# proiect_tsc_v49.net
KiCad netlist of a schematic drawn in EAGLE
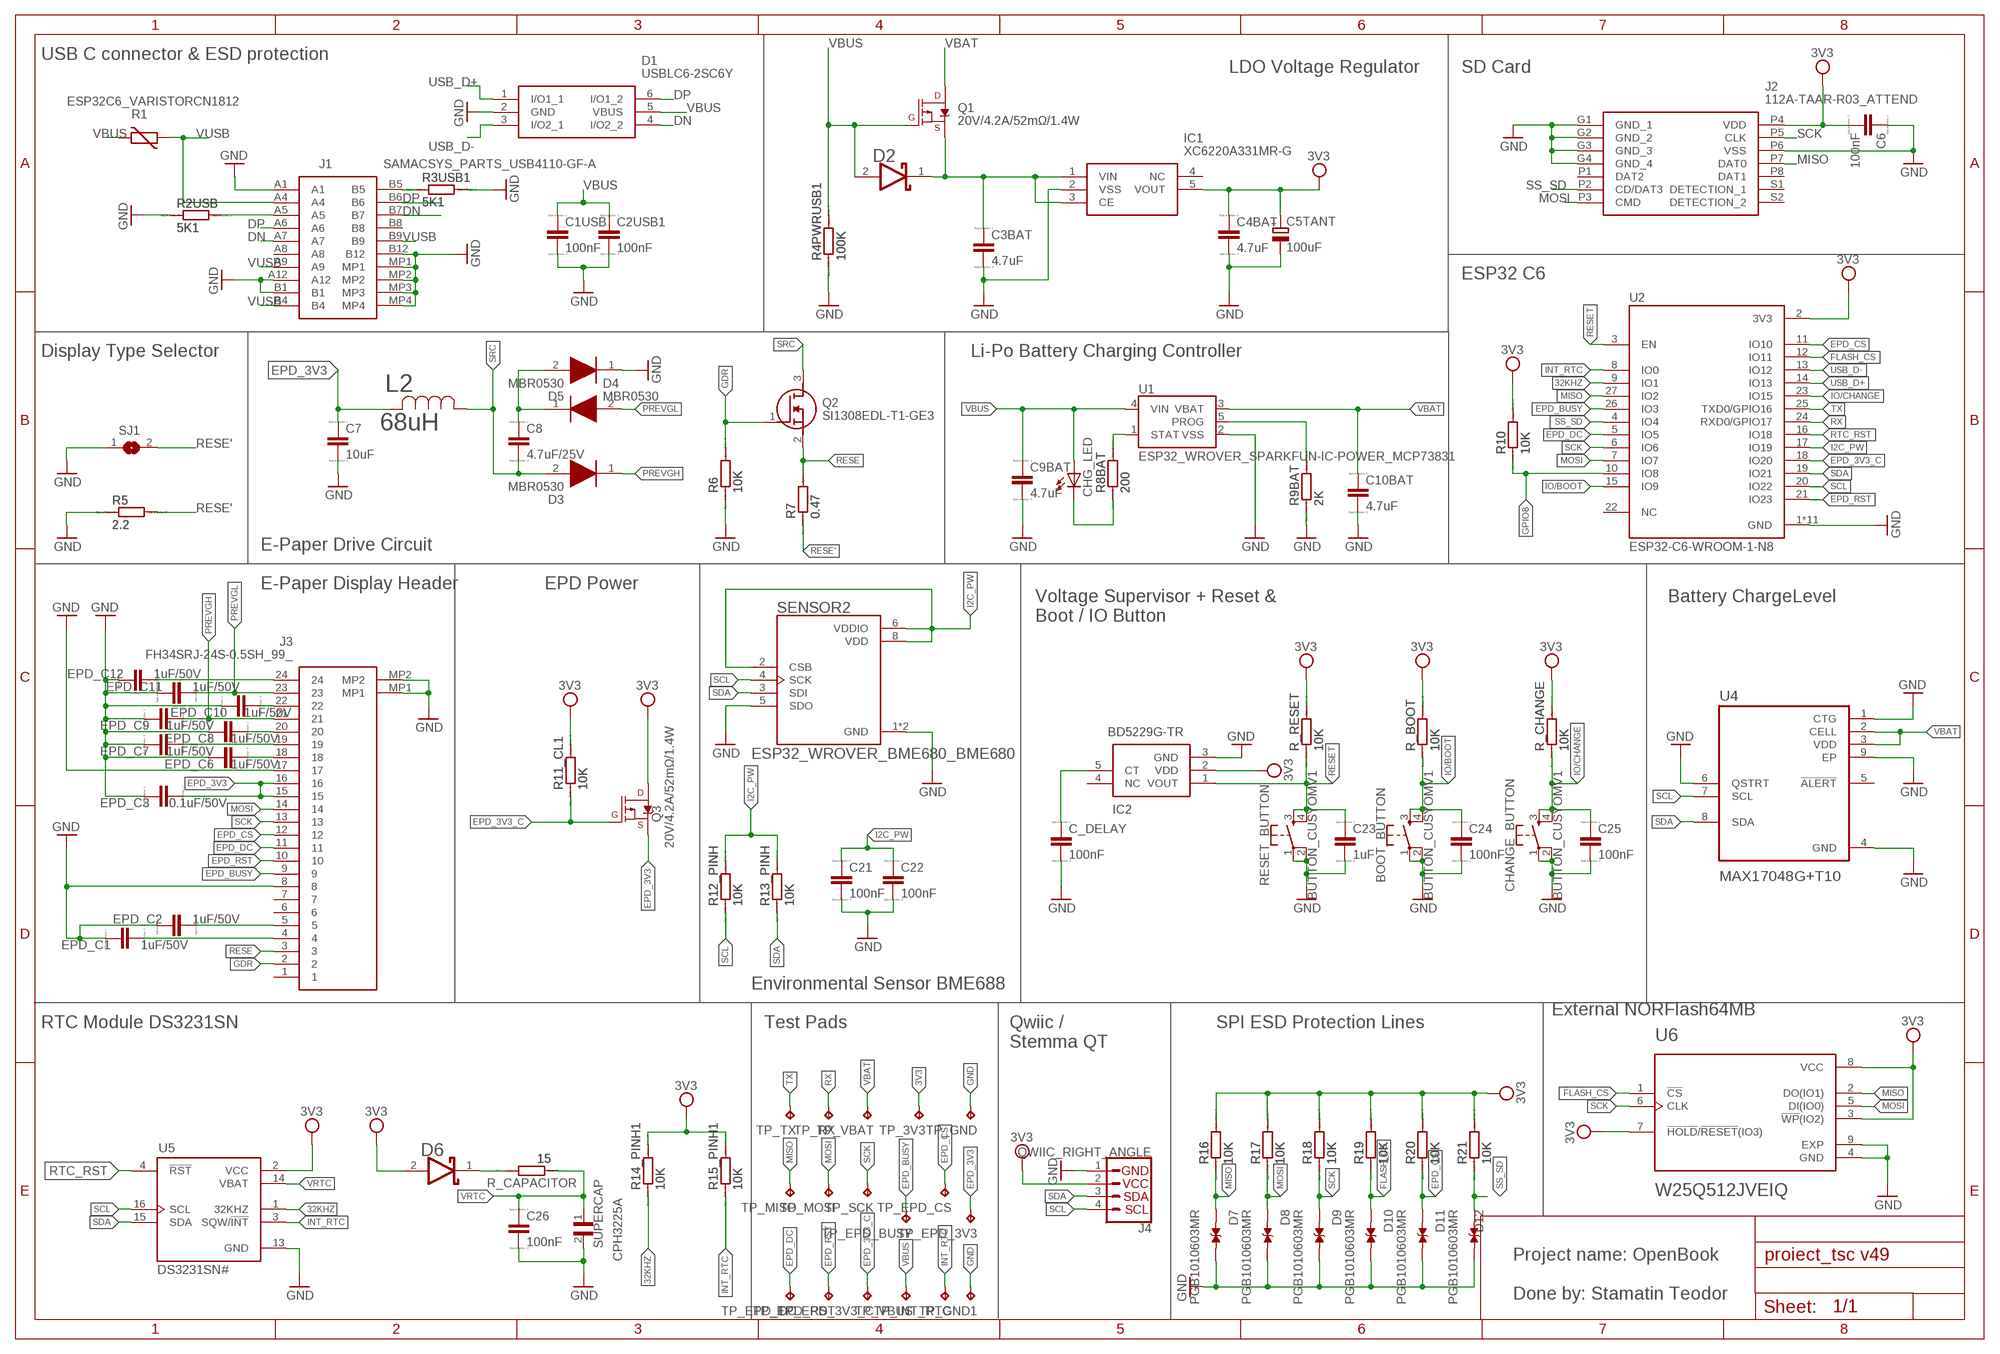
[diagram p0: schematic, sheet 1]

(export (version "E")
  (design (tool "Eeschema 10.0.6"))
  (components
    (comp (ref "BOOT_BUTTON")
      (value "BUTTON_CUSYOMV1")
      (footprint "eagle-import:MYBUTTON")
      (libsource (lib "eagle-import") (part "BUTTON_CUSYOMV1"))
    )
    (comp (ref "C1USB")
      (value "100nF")
      (footprint "eagle-import:ESP32_WROVER_EAGLE-LTSPICE_C0402")
      (libsource (lib "eagle-import") (part "EAGLE-LTSPICE_CC0402"))
    )
    (comp (ref "C2USB1")
      (value "100nF")
      (footprint "eagle-import:ESP32_WROVER_EAGLE-LTSPICE_C0402")
      (libsource (lib "eagle-import") (part "EAGLE-LTSPICE_CC0402"))
    )
    (comp (ref "C3BAT")
      (value "4.7uF")
      (footprint "eagle-import:ESP32_WROVER_EAGLE-LTSPICE_C0402")
      (libsource (lib "eagle-import") (part "EAGLE-LTSPICE_CC0402"))
    )
    (comp (ref "C4BAT")
      (value "4.7uF")
      (footprint "eagle-import:ESP32_WROVER_EAGLE-LTSPICE_C0402")
      (libsource (lib "eagle-import") (part "EAGLE-LTSPICE_CC0402"))
    )
    (comp (ref "C5TANT")
      (value "100uF")
      (footprint "eagle-import:RCL_CT3528")
      (libsource (lib "eagle-import") (part "RCL_CPOL-EUCT3528"))
    )
    (comp (ref "C6")
      (value "100nF")
      (footprint "eagle-import:ESP32_WROVER_EAGLE-LTSPICE_C0402")
      (libsource (lib "eagle-import") (part "EAGLE-LTSPICE_CC0402"))
    )
    (comp (ref "C7")
      (value "10uF")
      (footprint "eagle-import:ESP32_WROVER_EAGLE-LTSPICE_C0402")
      (libsource (lib "eagle-import") (part "EAGLE-LTSPICE_CC0402"))
    )
    (comp (ref "C8")
      (value "4.7uF/25V")
      (footprint "eagle-import:ESP32_WROVER_EAGLE-LTSPICE_C0402")
      (libsource (lib "eagle-import") (part "EAGLE-LTSPICE_CC0402"))
    )
    (comp (ref "C9BAT")
      (value "4.7uF")
      (footprint "eagle-import:ESP32_WROVER_EAGLE-LTSPICE_C0402")
      (libsource (lib "eagle-import") (part "EAGLE-LTSPICE_CC0402"))
    )
    (comp (ref "C10BAT")
      (value "4.7uF")
      (footprint "eagle-import:ESP32_WROVER_EAGLE-LTSPICE_C0402")
      (libsource (lib "eagle-import") (part "EAGLE-LTSPICE_CC0402"))
    )
    (comp (ref "C21")
      (value "100nF")
      (footprint "eagle-import:ESP32_WROVER_EAGLE-LTSPICE_C0402")
      (libsource (lib "eagle-import") (part "EAGLE-LTSPICE_CC0402"))
    )
    (comp (ref "C22")
      (value "100nF")
      (footprint "eagle-import:ESP32_WROVER_EAGLE-LTSPICE_C0402")
      (libsource (lib "eagle-import") (part "EAGLE-LTSPICE_CC0402"))
    )
    (comp (ref "C23")
      (value "1uF")
      (footprint "eagle-import:ESP32_WROVER_EAGLE-LTSPICE_C0402")
      (libsource (lib "eagle-import") (part "EAGLE-LTSPICE_CC0402"))
    )
    (comp (ref "C24")
      (value "100nF")
      (footprint "eagle-import:ESP32_WROVER_EAGLE-LTSPICE_C0402")
      (libsource (lib "eagle-import") (part "EAGLE-LTSPICE_CC0402"))
    )
    (comp (ref "C25")
      (value "100nF")
      (footprint "eagle-import:ESP32_WROVER_EAGLE-LTSPICE_C0402")
      (libsource (lib "eagle-import") (part "EAGLE-LTSPICE_CC0402"))
    )
    (comp (ref "C26")
      (value "100nF")
      (footprint "eagle-import:ESP32_WROVER_EAGLE-LTSPICE_C0402")
      (libsource (lib "eagle-import") (part "EAGLE-LTSPICE_CC0402"))
    )
    (comp (ref "CHANGE_BUTTON")
      (value "BUTTON_CUSYOMV1")
      (footprint "eagle-import:MYBUTTON")
      (libsource (lib "eagle-import") (part "BUTTON_CUSYOMV1"))
    )
    (comp (ref "CHG_LED")
      (value "ADAFRUIT_LEDCHIP-LED0603")
      (footprint "eagle-import:ADAFRUIT_CHIP-LED0603")
      (libsource (lib "eagle-import") (part "ADAFRUIT_LEDCHIP-LED0603"))
    )
    (comp (ref "C_DELAY")
      (value "100nF")
      (footprint "eagle-import:ESP32_WROVER_EAGLE-LTSPICE_C0402")
      (libsource (lib "eagle-import") (part "EAGLE-LTSPICE_CC0402"))
    )
    (comp (ref "D1")
      (value "USBLC6-2SC6Y")
      (footprint "eagle-import:SOT95P280X145-6N")
      (fields (field (name "MF") "STMicroelectronics"))
      (libsource (lib "eagle-import") (part "USBLC6-2SC6Y"))
    )
    (comp (ref "D2")
      (value "ESP32_WROVER_AVX---SD0805S020S1R0_AVX_SD0805S020S1R0_0_0AVX_SD0805S020S1R0_0_0")
      (footprint "eagle-import:ESP32_WROVER_AVX---SD0805S020S1R0_AVX_SD0805S020S1R0_0")
      (fields
        (field (name "DIGIKEY_PART_NUMBER") "478-7800-1-ND")
        (field (name "MF") "AVX")
        (field (name "MOUSER_PART_NUMBER") "581-SD0805S020S1R0")
      )
      (libsource (lib "eagle-import") (part "ESP32_WROVER_AVX---SD0805S020S1R0_AVX_SD0805S020S1R0_0_0AVX_SD0805S020S1R0_0_0"))
    )
    (comp (ref "D3")
      (value "MBR0530")
      (footprint "eagle-import:SOD3716X135N")
      (fields (field (name "MF") "ON Semiconductor"))
      (libsource (lib "eagle-import") (part "MBR0530"))
    )
    (comp (ref "D4")
      (value "MBR0530")
      (footprint "eagle-import:SOD3716X135N")
      (fields (field (name "MF") "ON Semiconductor"))
      (libsource (lib "eagle-import") (part "MBR0530"))
    )
    (comp (ref "D5")
      (value "MBR0530")
      (footprint "eagle-import:SOD3716X135N")
      (fields (field (name "MF") "ON Semiconductor"))
      (libsource (lib "eagle-import") (part "MBR0530"))
    )
    (comp (ref "D6")
      (value "ESP32_WROVER_AVX---SD0805S020S1R0_AVX_SD0805S020S1R0_0_0AVX_SD0805S020S1R0_0_0")
      (footprint "eagle-import:ESP32_WROVER_AVX---SD0805S020S1R0_AVX_SD0805S020S1R0_0")
      (fields
        (field (name "DIGIKEY_PART_NUMBER") "478-7800-1-ND")
        (field (name "MF") "AVX")
        (field (name "MOUSER_PART_NUMBER") "581-SD0805S020S1R0")
      )
      (libsource (lib "eagle-import") (part "ESP32_WROVER_AVX---SD0805S020S1R0_AVX_SD0805S020S1R0_0_0AVX_SD0805S020S1R0_0_0"))
    )
    (comp (ref "D7")
      (value "PGB1010603MR")
      (footprint "eagle-import:DIOC1608X36N")
      (fields (field (name "MF") "Littelfuse Inc."))
      (libsource (lib "eagle-import") (part "PGB1010603MR"))
    )
    (comp (ref "D8")
      (value "PGB1010603MR")
      (footprint "eagle-import:DIOC1608X36N")
      (fields (field (name "MF") "Littelfuse Inc."))
      (libsource (lib "eagle-import") (part "PGB1010603MR"))
    )
    (comp (ref "D9")
      (value "PGB1010603MR")
      (footprint "eagle-import:DIOC1608X36N")
      (fields (field (name "MF") "Littelfuse Inc."))
      (libsource (lib "eagle-import") (part "PGB1010603MR"))
    )
    (comp (ref "D10")
      (value "PGB1010603MR")
      (footprint "eagle-import:DIOC1608X36N")
      (fields (field (name "MF") "Littelfuse Inc."))
      (libsource (lib "eagle-import") (part "PGB1010603MR"))
    )
    (comp (ref "D11")
      (value "PGB1010603MR")
      (footprint "eagle-import:DIOC1608X36N")
      (fields (field (name "MF") "Littelfuse Inc."))
      (libsource (lib "eagle-import") (part "PGB1010603MR"))
    )
    (comp (ref "D12")
      (value "PGB1010603MR")
      (footprint "eagle-import:DIOC1608X36N")
      (fields (field (name "MF") "Littelfuse Inc."))
      (libsource (lib "eagle-import") (part "PGB1010603MR"))
    )
    (comp (ref "EPD_C1")
      (value "1uF/50V")
      (footprint "eagle-import:ESP32_WROVER_EAGLE-LTSPICE_C0402")
      (libsource (lib "eagle-import") (part "EAGLE-LTSPICE_CC0402"))
    )
    (comp (ref "EPD_C2")
      (value "1uF/50V")
      (footprint "eagle-import:ESP32_WROVER_EAGLE-LTSPICE_C0402")
      (libsource (lib "eagle-import") (part "EAGLE-LTSPICE_CC0402"))
    )
    (comp (ref "EPD_C3")
      (value "0.1uF/50V")
      (footprint "eagle-import:ESP32_WROVER_EAGLE-LTSPICE_C0402")
      (libsource (lib "eagle-import") (part "EAGLE-LTSPICE_CC0402"))
    )
    (comp (ref "EPD_C6")
      (value "1uF/50V")
      (footprint "eagle-import:ESP32_WROVER_EAGLE-LTSPICE_C0402")
      (libsource (lib "eagle-import") (part "EAGLE-LTSPICE_CC0402"))
    )
    (comp (ref "EPD_C7")
      (value "1uF/50V")
      (footprint "eagle-import:ESP32_WROVER_EAGLE-LTSPICE_C0402")
      (libsource (lib "eagle-import") (part "EAGLE-LTSPICE_CC0402"))
    )
    (comp (ref "EPD_C8")
      (value "1uF/50V")
      (footprint "eagle-import:ESP32_WROVER_EAGLE-LTSPICE_C0402")
      (libsource (lib "eagle-import") (part "EAGLE-LTSPICE_CC0402"))
    )
    (comp (ref "EPD_C9")
      (value "1uF/50V")
      (footprint "eagle-import:ESP32_WROVER_EAGLE-LTSPICE_C0402")
      (libsource (lib "eagle-import") (part "EAGLE-LTSPICE_CC0402"))
    )
    (comp (ref "EPD_C10")
      (value "1uF/50V")
      (footprint "eagle-import:ESP32_WROVER_EAGLE-LTSPICE_C0402")
      (libsource (lib "eagle-import") (part "EAGLE-LTSPICE_CC0402"))
    )
    (comp (ref "EPD_C11")
      (value "1uF/50V")
      (footprint "eagle-import:ESP32_WROVER_EAGLE-LTSPICE_C0402")
      (libsource (lib "eagle-import") (part "EAGLE-LTSPICE_CC0402"))
    )
    (comp (ref "EPD_C12")
      (value "1uF/50V")
      (footprint "eagle-import:ESP32_WROVER_EAGLE-LTSPICE_C0402")
      (libsource (lib "eagle-import") (part "EAGLE-LTSPICE_CC0402"))
    )
    (comp (ref "IC1")
      (value "XC6220A331MR-G")
      (footprint "eagle-import:SOT95P280X120-5N")
      (fields (field (name "MOUSER_PART_NUMBER") "865-XC6220A331MR-G"))
      (libsource (lib "eagle-import") (part "XC6220A331MR-G"))
    )
    (comp (ref "IC2")
      (value "BD5229G-TR")
      (footprint "eagle-import:SOT95P280X125-5N")
      (fields (field (name "MOUSER_PART_NUMBER") "755-BD5229G-TR"))
      (libsource (lib "eagle-import") (part "BD5229G-TR"))
    )
    (comp (ref "J1")
      (value "SAMACSYS_PARTS_USB4110-GF-A")
      (footprint "eagle-import:SAMACSYS_PARTS_USB4110GFA")
      (fields
        (field (name "MANUFACTURER_PART_NUMBER") "USB4110-GF-A")
        (field (name "MOUSER_PART_NUMBER") "640-USB4110-GF-A")
      )
      (libsource (lib "eagle-import") (part "SAMACSYS_PARTS_USB4110-GF-A"))
    )
    (comp (ref "J2")
      (value "112A-TAAR-R03_ATTEND")
      (footprint "eagle-import:112ATAARR03ATTEND")
      (fields (field (name "MANUFACTURER_PART_NUMBER") "112A-TAAR-R03 ATTEND"))
      (libsource (lib "eagle-import") (part "112A-TAAR-R03_ATTEND"))
    )
    (comp (ref "J3")
      (value "FH34SRJ-24S-0.5SH_99_")
      (footprint "eagle-import:FH34SRJ24S05SH99")
      (fields
        (field (name "MANUFACTURER_PART_NUMBER") "FH34SRJ-24S-0.5SH(99)")
        (field (name "MOUSER_PART_NUMBER") "798-FH34SRJ24S05SH99")
      )
      (libsource (lib "eagle-import") (part "FH34SRJ-24S-0.5SH_99_"))
    )
    (comp (ref "J4")
      (value "QWIIC_RIGHT_ANGLE")
      (footprint "eagle-import:JST04_1MM_RA")
      (libsource (lib "eagle-import") (part "QWIIC_CONNECTORJS-1MM"))
    )
    (comp (ref "L2")
      (value "68uH")
      (footprint "eagle-import:IND_4828-WE-TPC_WRE")
      (fields
        (field (name "MANUFACTURER_PART_NUMBER") "744043680")
        (field (name "COPYRIGHT") "Copyright (C) 2024 Ultra Librarian. All rights reserved.")
      )
      (libsource (lib "eagle-import") (part "744043680IND_4828-WE-TPC_WRE"))
    )
    (comp (ref "Q1")
      (value "20V/4.2A/52mΩ/1.4W")
      (footprint "eagle-import:ESP32_WROVER_SPARKFUN-DISCRETESEMI_SOT23-3")
      (libsource (lib "eagle-import") (part "ESP32_WROVER_SPARKFUN-DISCRETESEMI_MOSFET_PCH-DMG2305UX-7"))
    )
    (comp (ref "Q2")
      (value "SI1308EDL-T1-GE3")
      (footprint "eagle-import:SOT65P210X110-3N")
      (fields (field (name "MF") "Vishay Siliconix"))
      (libsource (lib "eagle-import") (part "SI1308EDL-T1-GE3"))
    )
    (comp (ref "Q3")
      (value "20V/4.2A/52mΩ/1.4W")
      (footprint "eagle-import:ESP32_WROVER_SPARKFUN-DISCRETESEMI_SOT23-3")
      (libsource (lib "eagle-import") (part "ESP32_WROVER_SPARKFUN-DISCRETESEMI_MOSFET_PCH-DMG2305UX-7"))
    )
    (comp (ref "R1")
      (value "ESP32C6_VARISTORCN1812")
      (footprint "eagle-import:ESP32C6_VARISTOR_CT_CN1812")
      (libsource (lib "eagle-import") (part "ESP32C6_VARISTORCN1812"))
    )
    (comp (ref "R2USB")
      (value "5K1")
      (footprint "eagle-import:ESP32_WROVER_EAGLE-LTSPICE_R0402")
      (libsource (lib "eagle-import") (part "ESP32_WROVER_EAGLE-LTSPICE_RR0402"))
    )
    (comp (ref "R3USB1")
      (value "5K1")
      (footprint "eagle-import:ESP32_WROVER_EAGLE-LTSPICE_R0402")
      (libsource (lib "eagle-import") (part "ESP32_WROVER_EAGLE-LTSPICE_RR0402"))
    )
    (comp (ref "R4PWRUSB1")
      (value "100K")
      (footprint "eagle-import:ESP32_WROVER_EAGLE-LTSPICE_R0402")
      (libsource (lib "eagle-import") (part "ESP32_WROVER_EAGLE-LTSPICE_RR0402"))
    )
    (comp (ref "R5")
      (value "2.2")
      (footprint "eagle-import:ESP32_WROVER_EAGLE-LTSPICE_R0402")
      (libsource (lib "eagle-import") (part "ESP32_WROVER_EAGLE-LTSPICE_RR0402"))
    )
    (comp (ref "R6")
      (value "10K")
      (footprint "eagle-import:ESP32_WROVER_EAGLE-LTSPICE_R0402")
      (libsource (lib "eagle-import") (part "ESP32_WROVER_EAGLE-LTSPICE_RR0402"))
    )
    (comp (ref "R7")
      (value "0.47")
      (footprint "eagle-import:ESP32_WROVER_EAGLE-LTSPICE_R0402")
      (libsource (lib "eagle-import") (part "ESP32_WROVER_EAGLE-LTSPICE_RR0402"))
    )
    (comp (ref "R8BAT")
      (value "200")
      (footprint "eagle-import:ESP32_WROVER_EAGLE-LTSPICE_R0402")
      (libsource (lib "eagle-import") (part "ESP32_WROVER_EAGLE-LTSPICE_RR0402"))
    )
    (comp (ref "R9BAT")
      (value "2K")
      (footprint "eagle-import:ESP32_WROVER_EAGLE-LTSPICE_R0402")
      (libsource (lib "eagle-import") (part "ESP32_WROVER_EAGLE-LTSPICE_RR0402"))
    )
    (comp (ref "R10")
      (value "10K")
      (footprint "eagle-import:ESP32_WROVER_EAGLE-LTSPICE_R0402")
      (libsource (lib "eagle-import") (part "ESP32_WROVER_EAGLE-LTSPICE_RR0402"))
    )
    (comp (ref "R11_CL1")
      (value "10K")
      (footprint "eagle-import:ESP32_WROVER_EAGLE-LTSPICE_R0402")
      (libsource (lib "eagle-import") (part "ESP32_WROVER_EAGLE-LTSPICE_RR0402"))
    )
    (comp (ref "R12_PINH")
      (value "10K")
      (footprint "eagle-import:ESP32_WROVER_EAGLE-LTSPICE_R0402")
      (libsource (lib "eagle-import") (part "ESP32_WROVER_EAGLE-LTSPICE_RR0402"))
    )
    (comp (ref "R13_PINH")
      (value "10K")
      (footprint "eagle-import:ESP32_WROVER_EAGLE-LTSPICE_R0402")
      (libsource (lib "eagle-import") (part "ESP32_WROVER_EAGLE-LTSPICE_RR0402"))
    )
    (comp (ref "R14_PINH1")
      (value "10K")
      (footprint "eagle-import:ESP32_WROVER_EAGLE-LTSPICE_R0402")
      (libsource (lib "eagle-import") (part "ESP32_WROVER_EAGLE-LTSPICE_RR0402"))
    )
    (comp (ref "R15_PINH1")
      (value "10K")
      (footprint "eagle-import:ESP32_WROVER_EAGLE-LTSPICE_R0402")
      (libsource (lib "eagle-import") (part "ESP32_WROVER_EAGLE-LTSPICE_RR0402"))
    )
    (comp (ref "R16")
      (value "10K")
      (footprint "eagle-import:ESP32_WROVER_EAGLE-LTSPICE_R0402")
      (libsource (lib "eagle-import") (part "ESP32_WROVER_EAGLE-LTSPICE_RR0402"))
    )
    (comp (ref "R17")
      (value "10K")
      (footprint "eagle-import:ESP32_WROVER_EAGLE-LTSPICE_R0402")
      (libsource (lib "eagle-import") (part "ESP32_WROVER_EAGLE-LTSPICE_RR0402"))
    )
    (comp (ref "R18")
      (value "10K")
      (footprint "eagle-import:ESP32_WROVER_EAGLE-LTSPICE_R0402")
      (libsource (lib "eagle-import") (part "ESP32_WROVER_EAGLE-LTSPICE_RR0402"))
    )
    (comp (ref "R19")
      (value "10K")
      (footprint "eagle-import:ESP32_WROVER_EAGLE-LTSPICE_R0402")
      (libsource (lib "eagle-import") (part "ESP32_WROVER_EAGLE-LTSPICE_RR0402"))
    )
    (comp (ref "R20")
      (value "10K")
      (footprint "eagle-import:ESP32_WROVER_EAGLE-LTSPICE_R0402")
      (libsource (lib "eagle-import") (part "ESP32_WROVER_EAGLE-LTSPICE_RR0402"))
    )
    (comp (ref "R21")
      (value "10K")
      (footprint "eagle-import:ESP32_WROVER_EAGLE-LTSPICE_R0402")
      (libsource (lib "eagle-import") (part "ESP32_WROVER_EAGLE-LTSPICE_RR0402"))
    )
    (comp (ref "RESET_BUTTON")
      (value "BUTTON_CUSYOMV1")
      (footprint "eagle-import:MYBUTTON")
      (libsource (lib "eagle-import") (part "BUTTON_CUSYOMV1"))
    )
    (comp (ref "R_BOOT")
      (value "10K")
      (footprint "eagle-import:ESP32_WROVER_EAGLE-LTSPICE_R0402")
      (libsource (lib "eagle-import") (part "ESP32_WROVER_EAGLE-LTSPICE_RR0402"))
    )
    (comp (ref "R_CAPACITOR")
      (value "15")
      (footprint "eagle-import:ESP32_WROVER_EAGLE-LTSPICE_R0402")
      (libsource (lib "eagle-import") (part "ESP32_WROVER_EAGLE-LTSPICE_RR0402"))
    )
    (comp (ref "R_CHANGE")
      (value "10K")
      (footprint "eagle-import:ESP32_WROVER_EAGLE-LTSPICE_R0402")
      (libsource (lib "eagle-import") (part "ESP32_WROVER_EAGLE-LTSPICE_RR0402"))
    )
    (comp (ref "R_RESET")
      (value "10K")
      (footprint "eagle-import:ESP32_WROVER_EAGLE-LTSPICE_R0402")
      (libsource (lib "eagle-import") (part "ESP32_WROVER_EAGLE-LTSPICE_RR0402"))
    )
    (comp (ref "SENSOR2")
      (value "ESP32_WROVER_BME680_BME680")
      (footprint "eagle-import:ESP32_WROVER_BME680_PSON80P300X300X100-8N")
      (fields (field (name "MF") "Bosch Sensortec") (field (name "MP") "BME680"))
      (libsource (lib "eagle-import") (part "ESP32_WROVER_BME680_BME680"))
    )
    (comp (ref "SJ1") (value "SJ") (footprint "eagle-import:SJ") (libsource (lib "eagle-import") (part "SJ")))
    (comp (ref "SUPERCAP")
      (value "CPH3225A")
      (footprint "eagle-import:CAPCP3225X100N")
      (fields (field (name "MF") "Seiko Instruments"))
      (libsource (lib "eagle-import") (part "CPH3225A"))
    )
    (comp (ref "TP_3V3")
      (value "TPTP20R")
      (footprint "eagle-import:TP20R")
      (libsource (lib "eagle-import") (part "TPTP20R"))
    )
    (comp (ref "TP_EPD_3V3")
      (value "TPTP20R")
      (footprint "eagle-import:TP20R")
      (libsource (lib "eagle-import") (part "TPTP20R"))
    )
    (comp (ref "TP_EPD_3V3_C")
      (value "TPTP20R")
      (footprint "eagle-import:TP20R")
      (libsource (lib "eagle-import") (part "TPTP20R"))
    )
    (comp (ref "TP_EPD_BUSY")
      (value "TPTP20R")
      (footprint "eagle-import:TP20R")
      (libsource (lib "eagle-import") (part "TPTP20R"))
    )
    (comp (ref "TP_EPD_CS")
      (value "TPTP20R")
      (footprint "eagle-import:TP20R")
      (libsource (lib "eagle-import") (part "TPTP20R"))
    )
    (comp (ref "TP_EPD_DC")
      (value "TPTP20R")
      (footprint "eagle-import:TP20R")
      (libsource (lib "eagle-import") (part "TPTP20R"))
    )
    (comp (ref "TP_EPD_RST")
      (value "TPTP20R")
      (footprint "eagle-import:TP20R")
      (libsource (lib "eagle-import") (part "TPTP20R"))
    )
    (comp (ref "TP_GND")
      (value "TPTP20R")
      (footprint "eagle-import:TP20R")
      (libsource (lib "eagle-import") (part "TPTP20R"))
    )
    (comp (ref "TP_GND1")
      (value "TPTP20R")
      (footprint "eagle-import:TP20R")
      (libsource (lib "eagle-import") (part "TPTP20R"))
    )
    (comp (ref "TP_INT_RTC")
      (value "TPTP20R")
      (footprint "eagle-import:TP20R")
      (libsource (lib "eagle-import") (part "TPTP20R"))
    )
    (comp (ref "TP_MISO")
      (value "TPTP20R")
      (footprint "eagle-import:TP20R")
      (libsource (lib "eagle-import") (part "TPTP20R"))
    )
    (comp (ref "TP_MOSI")
      (value "TPTP20R")
      (footprint "eagle-import:TP20R")
      (libsource (lib "eagle-import") (part "TPTP20R"))
    )
    (comp (ref "TP_RX")
      (value "TPTP20R")
      (footprint "eagle-import:TP20R")
      (libsource (lib "eagle-import") (part "TPTP20R"))
    )
    (comp (ref "TP_SCK")
      (value "TPTP20R")
      (footprint "eagle-import:TP20R")
      (libsource (lib "eagle-import") (part "TPTP20R"))
    )
    (comp (ref "TP_TX")
      (value "TPTP20R")
      (footprint "eagle-import:TP20R")
      (libsource (lib "eagle-import") (part "TPTP20R"))
    )
    (comp (ref "TP_VBAT")
      (value "TPTP20R")
      (footprint "eagle-import:TP20R")
      (libsource (lib "eagle-import") (part "TPTP20R"))
    )
    (comp (ref "TP_VBUS")
      (value "TPTP20R")
      (footprint "eagle-import:TP20R")
      (libsource (lib "eagle-import") (part "TPTP20R"))
    )
    (comp (ref "U1")
      (value "ESP32_WROVER_SPARKFUN-IC-POWER_MCP73831")
      (footprint "eagle-import:ESP32_WROVER_SPARKFUN-IC-POWER_SOT23-5")
      (libsource (lib "eagle-import") (part "ESP32_WROVER_SPARKFUN-IC-POWER_MCP73831"))
    )
    (comp (ref "U2")
      (value "ESP32-C6-WROOM-1-N8")
      (footprint "eagle-import:XCVR_ESP32-C6-WROOM-1-N8")
      (fields (field (name "MF") "Espressif Systems"))
      (libsource (lib "eagle-import") (part "ESP32-C6-WROOM-1-N8"))
    )
    (comp (ref "U4")
      (value "MAX17048G+T10")
      (footprint "eagle-import:SON50P200X200X80-9N")
      (fields (field (name "MF") "Analog Devices"))
      (libsource (lib "eagle-import") (part "MAX17048G+T10"))
    )
    (comp (ref "U5")
      (value "DS3231SN#")
      (footprint "eagle-import:SOIC127P1032X265-16N")
      (fields (field (name "MF") "Analog Devices"))
      (libsource (lib "eagle-import") (part "DS3231SN#"))
    )
    (comp (ref "U6")
      (value "W25Q512JVEIQ")
      (footprint "eagle-import:SON127P600X800X80-9N")
      (fields (field (name "MF") "Winbond Electronics"))
      (libsource (lib "eagle-import") (part "W25Q512JVEIQ"))
    )
  )
  (nets
    (net (code "1") (name "/DN") (class "Default")
      (node (ref "D1") (pin "4") (pinfunction "I/O2_2_4") (pintype "bidirectional"))
      (node (ref "J1") (pin "A7") (pinfunction "A7_A7") (pintype "bidirectional"))
      (node (ref "J1") (pin "B7") (pinfunction "B7_B7") (pintype "bidirectional"))
    )
    (net (code "2") (name "/DP") (class "Default")
      (node (ref "D1") (pin "6") (pinfunction "I/O1_2_6") (pintype "bidirectional"))
      (node (ref "J1") (pin "A6") (pinfunction "A6_A6") (pintype "bidirectional"))
      (node (ref "J1") (pin "B6") (pinfunction "B6_B6") (pintype "bidirectional"))
    )
    (net (code "3") (name "/VUSB") (class "Default")
      (node (ref "J1") (pin "A4") (pinfunction "A4_A4") (pintype "bidirectional"))
      (node (ref "J1") (pin "A9") (pinfunction "A9_A9") (pintype "bidirectional"))
      (node (ref "J1") (pin "B4") (pinfunction "B4_B4") (pintype "bidirectional"))
      (node (ref "J1") (pin "B9") (pinfunction "B9_B9") (pintype "bidirectional"))
      (node (ref "R1") (pin "1") (pinfunction "1_1") (pintype "passive"))
    )
    (net (code "4") (name "3V3") (class "Default")
      (node (ref "C4BAT") (pin "1") (pinfunction "1_1") (pintype "passive"))
      (node (ref "C5TANT") (pin "+") (pinfunction "+_+") (pintype "passive"))
      (node (ref "C6") (pin "2") (pinfunction "2_2") (pintype "passive"))
      (node (ref "D6") (pin "2") (pinfunction "ANODE_2") (pintype "bidirectional"))
      (node (ref "IC1") (pin "5") (pinfunction "VOUT_5") (pintype "bidirectional"))
      (node (ref "IC2") (pin "2") (pinfunction "VDD_2") (pintype "bidirectional"))
      (node (ref "J2") (pin "P4") (pinfunction "VDD_P4") (pintype "bidirectional"))
      (node (ref "J4") (pin "2") (pinfunction "2_2") (pintype "power_in"))
      (node (ref "Q3") (pin "3") (pinfunction "D_3") (pintype "bidirectional"))
      (node (ref "R10") (pin "2") (pinfunction "2_2") (pintype "passive"))
      (node (ref "R11_CL1") (pin "2") (pinfunction "2_2") (pintype "passive"))
      (node (ref "R14_PINH1") (pin "2") (pinfunction "2_2") (pintype "passive"))
      (node (ref "R15_PINH1") (pin "2") (pinfunction "2_2") (pintype "passive"))
      (node (ref "R16") (pin "2") (pinfunction "2_2") (pintype "passive"))
      (node (ref "R17") (pin "2") (pinfunction "2_2") (pintype "passive"))
      (node (ref "R18") (pin "2") (pinfunction "2_2") (pintype "passive"))
      (node (ref "R19") (pin "2") (pinfunction "2_2") (pintype "passive"))
      (node (ref "R20") (pin "2") (pinfunction "2_2") (pintype "passive"))
      (node (ref "R21") (pin "2") (pinfunction "2_2") (pintype "passive"))
      (node (ref "R_BOOT") (pin "2") (pinfunction "2_2") (pintype "passive"))
      (node (ref "R_CHANGE") (pin "2") (pinfunction "2_2") (pintype "passive"))
      (node (ref "R_RESET") (pin "2") (pinfunction "2_2") (pintype "passive"))
      (node (ref "TP_3V3") (pin "TP") (pinfunction "TP_TP") (pintype "input"))
      (node (ref "U2") (pin "2") (pinfunction "3V3_2") (pintype "power_in"))
      (node (ref "U5") (pin "2") (pinfunction "VCC_2") (pintype "power_in"))
      (node (ref "U6") (pin "3") (pinfunction "~{WP}(IO2)_3") (pintype "bidirectional"))
      (node (ref "U6") (pin "7") (pinfunction "~{HOLD}/~{RESET}(IO3)_7") (pintype "bidirectional"))
      (node (ref "U6") (pin "8") (pinfunction "VCC_8") (pintype "power_in"))
    )
    (net (code "5") (name "32KHZ") (class "Default")
      (node (ref "R14_PINH1") (pin "1") (pinfunction "1_1") (pintype "passive"))
      (node (ref "U2") (pin "9") (pinfunction "IO1_9") (pintype "bidirectional"))
      (node (ref "U5") (pin "1") (pinfunction "32KHZ_1") (pintype "output"))
    )
    (net (code "6") (name "EPD_3V3") (class "Default")
      (node (ref "C7") (pin "1") (pinfunction "1_1") (pintype "passive"))
      (node (ref "EPD_C3") (pin "2") (pinfunction "2_2") (pintype "passive"))
      (node (ref "J3") (pin "15") (pinfunction "15_15") (pintype "bidirectional"))
      (node (ref "J3") (pin "16") (pinfunction "16_16") (pintype "bidirectional"))
      (node (ref "L2") (pin "2") (pinfunction "2_2") (pintype "passive"))
      (node (ref "Q3") (pin "2") (pinfunction "S_2") (pintype "bidirectional"))
      (node (ref "TP_EPD_3V3") (pin "TP") (pinfunction "TP_TP") (pintype "input"))
    )
    (net (code "7") (name "EPD_3V3_C") (class "Default")
      (node (ref "Q3") (pin "1") (pinfunction "G_1") (pintype "bidirectional"))
      (node (ref "R11_CL1") (pin "1") (pinfunction "1_1") (pintype "passive"))
      (node (ref "TP_EPD_3V3_C") (pin "TP") (pinfunction "TP_TP") (pintype "input"))
      (node (ref "U2") (pin "18") (pinfunction "IO20_18") (pintype "bidirectional"))
    )
    (net (code "8") (name "EPD_BUSY") (class "Default")
      (node (ref "J3") (pin "9") (pinfunction "9_9") (pintype "bidirectional"))
      (node (ref "TP_EPD_BUSY") (pin "TP") (pinfunction "TP_TP") (pintype "input"))
      (node (ref "U2") (pin "26") (pinfunction "IO3_26") (pintype "bidirectional"))
    )
    (net (code "9") (name "EPD_CS") (class "Default")
      (node (ref "D11") (pin "1") (pinfunction "1_1") (pintype "passive"))
      (node (ref "J3") (pin "12") (pinfunction "12_12") (pintype "bidirectional"))
      (node (ref "R20") (pin "1") (pinfunction "1_1") (pintype "passive"))
      (node (ref "TP_EPD_CS") (pin "TP") (pinfunction "TP_TP") (pintype "input"))
      (node (ref "U2") (pin "11") (pinfunction "IO10_11") (pintype "bidirectional"))
    )
    (net (code "10") (name "EPD_DC") (class "Default")
      (node (ref "J3") (pin "11") (pinfunction "11_11") (pintype "bidirectional"))
      (node (ref "TP_EPD_DC") (pin "TP") (pinfunction "TP_TP") (pintype "input"))
      (node (ref "U2") (pin "5") (pinfunction "IO5_5") (pintype "bidirectional"))
    )
    (net (code "11") (name "EPD_RST") (class "Default")
      (node (ref "J3") (pin "10") (pinfunction "10_10") (pintype "bidirectional"))
      (node (ref "TP_EPD_RST") (pin "TP") (pinfunction "TP_TP") (pintype "input"))
      (node (ref "U2") (pin "21") (pinfunction "IO23_21") (pintype "bidirectional"))
    )
    (net (code "12") (name "FLASH_CS") (class "Default")
      (node (ref "D10") (pin "1") (pinfunction "1_1") (pintype "passive"))
      (node (ref "R19") (pin "1") (pinfunction "1_1") (pintype "passive"))
      (node (ref "U2") (pin "12") (pinfunction "IO11_12") (pintype "bidirectional"))
      (node (ref "U6") (pin "1") (pinfunction "~{CS}_1") (pintype "input"))
    )
    (net (code "13") (name "GDR") (class "Default")
      (node (ref "J3") (pin "2") (pinfunction "2_2") (pintype "bidirectional"))
      (node (ref "Q2") (pin "1") (pinfunction "G_1") (pintype "bidirectional"))
      (node (ref "R6") (pin "2") (pinfunction "2_2") (pintype "passive"))
    )
    (net (code "14") (name "GND") (class "Default")
      (node (ref "BOOT_BUTTON") (pin "1") (pinfunction "1_1") (pintype "passive"))
      (node (ref "BOOT_BUTTON") (pin "2") (pinfunction "2_2") (pintype "passive"))
      (node (ref "C10BAT") (pin "2") (pinfunction "2_2") (pintype "passive"))
      (node (ref "C1USB") (pin "2") (pinfunction "2_2") (pintype "passive"))
      (node (ref "C21") (pin "2") (pinfunction "2_2") (pintype "passive"))
      (node (ref "C22") (pin "2") (pinfunction "2_2") (pintype "passive"))
      (node (ref "C23") (pin "2") (pinfunction "2_2") (pintype "passive"))
      (node (ref "C24") (pin "2") (pinfunction "2_2") (pintype "passive"))
      (node (ref "C25") (pin "2") (pinfunction "2_2") (pintype "passive"))
      (node (ref "C26") (pin "2") (pinfunction "2_2") (pintype "passive"))
      (node (ref "C2USB1") (pin "2") (pinfunction "2_2") (pintype "passive"))
      (node (ref "C3BAT") (pin "2") (pinfunction "2_2") (pintype "passive"))
      (node (ref "C4BAT") (pin "2") (pinfunction "2_2") (pintype "passive"))
      (node (ref "C5TANT") (pin "-") (pinfunction "-_-") (pintype "passive"))
      (node (ref "C6") (pin "1") (pinfunction "1_1") (pintype "passive"))
      (node (ref "C7") (pin "2") (pinfunction "2_2") (pintype "passive"))
      (node (ref "C9BAT") (pin "2") (pinfunction "2_2") (pintype "passive"))
      (node (ref "CHANGE_BUTTON") (pin "1") (pinfunction "1_1") (pintype "passive"))
      (node (ref "CHANGE_BUTTON") (pin "2") (pinfunction "2_2") (pintype "passive"))
      (node (ref "C_DELAY") (pin "2") (pinfunction "2_2") (pintype "passive"))
      (node (ref "D1") (pin "2") (pinfunction "GND_2") (pintype "bidirectional"))
      (node (ref "D10") (pin "2") (pinfunction "2_2") (pintype "passive"))
      (node (ref "D11") (pin "2") (pinfunction "2_2") (pintype "passive"))
      (node (ref "D12") (pin "2") (pinfunction "2_2") (pintype "passive"))
      (node (ref "D5") (pin "1") (pinfunction "K_1") (pintype "bidirectional"))
      (node (ref "D7") (pin "2") (pinfunction "2_2") (pintype "passive"))
      (node (ref "D8") (pin "2") (pinfunction "2_2") (pintype "passive"))
      (node (ref "D9") (pin "2") (pinfunction "2_2") (pintype "passive"))
      (node (ref "EPD_C1") (pin "1") (pinfunction "1_1") (pintype "passive"))
      (node (ref "EPD_C10") (pin "1") (pinfunction "1_1") (pintype "passive"))
      (node (ref "EPD_C11") (pin "1") (pinfunction "1_1") (pintype "passive"))
      (node (ref "EPD_C12") (pin "1") (pinfunction "1_1") (pintype "passive"))
      (node (ref "EPD_C2") (pin "1") (pinfunction "1_1") (pintype "passive"))
      (node (ref "EPD_C3") (pin "1") (pinfunction "1_1") (pintype "passive"))
      (node (ref "EPD_C6") (pin "1") (pinfunction "1_1") (pintype "passive"))
      (node (ref "EPD_C7") (pin "1") (pinfunction "1_1") (pintype "passive"))
      (node (ref "EPD_C8") (pin "1") (pinfunction "1_1") (pintype "passive"))
      (node (ref "EPD_C9") (pin "1") (pinfunction "1_1") (pintype "passive"))
      (node (ref "IC1") (pin "2") (pinfunction "VSS_2") (pintype "bidirectional"))
      (node (ref "IC2") (pin "3") (pinfunction "GND_3") (pintype "bidirectional"))
      (node (ref "J1") (pin "A1") (pinfunction "A1_A1") (pintype "bidirectional"))
      (node (ref "J1") (pin "A12") (pinfunction "A12_A12") (pintype "bidirectional"))
      (node (ref "J1") (pin "B1") (pinfunction "B1_B1") (pintype "bidirectional"))
      (node (ref "J1") (pin "B12") (pinfunction "B12_B12") (pintype "bidirectional"))
      (node (ref "J1") (pin "MP1") (pinfunction "MP1_MP1") (pintype "bidirectional"))
      (node (ref "J1") (pin "MP2") (pinfunction "MP2_MP2") (pintype "bidirectional"))
      (node (ref "J1") (pin "MP3") (pinfunction "MP3_MP3") (pintype "bidirectional"))
      (node (ref "J1") (pin "MP4") (pinfunction "MP4_MP4") (pintype "bidirectional"))
      (node (ref "J2") (pin "G1") (pinfunction "GND_1_G1") (pintype "bidirectional"))
      (node (ref "J2") (pin "G2") (pinfunction "GND_2_G2") (pintype "bidirectional"))
      (node (ref "J2") (pin "G3") (pinfunction "GND_3_G3") (pintype "bidirectional"))
      (node (ref "J2") (pin "G4") (pinfunction "GND_4_G4") (pintype "bidirectional"))
      (node (ref "J2") (pin "P6") (pinfunction "VSS_P6") (pintype "bidirectional"))
      (node (ref "J3") (pin "17") (pinfunction "17_17") (pintype "bidirectional"))
      (node (ref "J3") (pin "8") (pinfunction "8_8") (pintype "bidirectional"))
      (node (ref "J3") (pin "MP1") (pinfunction "MP1_MP1") (pintype "bidirectional"))
      (node (ref "J3") (pin "MP2") (pinfunction "MP2_MP2") (pintype "bidirectional"))
      (node (ref "J4") (pin "1") (pinfunction "1_1") (pintype "power_in"))
      (node (ref "R2USB") (pin "1") (pinfunction "1_1") (pintype "passive"))
      (node (ref "R3USB1") (pin "2") (pinfunction "2_2") (pintype "passive"))
      (node (ref "R4PWRUSB1") (pin "1") (pinfunction "1_1") (pintype "passive"))
      (node (ref "R5") (pin "1") (pinfunction "1_1") (pintype "passive"))
      (node (ref "R6") (pin "1") (pinfunction "1_1") (pintype "passive"))
      (node (ref "R9BAT") (pin "1") (pinfunction "1_1") (pintype "passive"))
      (node (ref "RESET_BUTTON") (pin "1") (pinfunction "1_1") (pintype "passive"))
      (node (ref "RESET_BUTTON") (pin "2") (pinfunction "2_2") (pintype "passive"))
      (node (ref "SENSOR2") (pin "1") (pinfunction "GND_1") (pintype "power_in"))
      (node (ref "SENSOR2") (pin "5") (pinfunction "SDO_5") (pintype "bidirectional"))
      (node (ref "SENSOR2") (pin "7") (pinfunction "GND_7") (pintype "power_in"))
      (node (ref "SJ1") (pin "1") (pinfunction "1_1") (pintype "passive"))
      (node (ref "SUPERCAP") (pin "2") (pinfunction "2_2") (pintype "passive"))
      (node (ref "TP_GND") (pin "TP") (pinfunction "TP_TP") (pintype "input"))
      (node (ref "TP_GND1") (pin "TP") (pinfunction "TP_TP") (pintype "input"))
      (node (ref "U1") (pin "2") (pinfunction "VSS_2") (pintype "power_in"))
      (node (ref "U2") (pin "1") (pinfunction "GND_1") (pintype "power_in"))
      (node (ref "U2") (pin "28") (pinfunction "GND_28") (pintype "power_in"))
      (node (ref "U2") (pin "29_1") (pinfunction "GND_29_1") (pintype "power_in"))
      (node (ref "U2") (pin "29_2") (pinfunction "GND_29_2") (pintype "power_in"))
      (node (ref "U2") (pin "29_3") (pinfunction "GND_29_3") (pintype "power_in"))
      (node (ref "U2") (pin "29_4") (pinfunction "GND_29_4") (pintype "power_in"))
      (node (ref "U2") (pin "29_5") (pinfunction "GND_29_5") (pintype "power_in"))
      (node (ref "U2") (pin "29_6") (pinfunction "GND_29_6") (pintype "power_in"))
      (node (ref "U2") (pin "29_7") (pinfunction "GND_29_7") (pintype "power_in"))
      (node (ref "U2") (pin "29_8") (pinfunction "GND_29_8") (pintype "power_in"))
      (node (ref "U2") (pin "29_9") (pinfunction "GND_29_9") (pintype "power_in"))
      (node (ref "U4") (pin "1") (pinfunction "CTG_1") (pintype "power_in"))
      (node (ref "U4") (pin "4") (pinfunction "GND_4") (pintype "power_in"))
      (node (ref "U4") (pin "6") (pinfunction "QSTRT_6") (pintype "input"))
      (node (ref "U4") (pin "9") (pinfunction "EP_9") (pintype "power_in"))
      (node (ref "U5") (pin "13") (pinfunction "GND_13") (pintype "power_in"))
      (node (ref "U6") (pin "4") (pinfunction "GND_4") (pintype "power_in"))
      (node (ref "U6") (pin "9") (pinfunction "EXP_9") (pintype "passive"))
    )
    (net (code "15") (name "GPIO8") (class "Default")
      (node (ref "R10") (pin "1") (pinfunction "1_1") (pintype "passive"))
      (node (ref "U2") (pin "10") (pinfunction "IO8_10") (pintype "bidirectional"))
    )
    (net (code "16") (name "I2C_PW") (class "Default")
      (node (ref "C21") (pin "1") (pinfunction "1_1") (pintype "passive"))
      (node (ref "C22") (pin "1") (pinfunction "1_1") (pintype "passive"))
      (node (ref "R12_PINH") (pin "2") (pinfunction "2_2") (pintype "passive"))
      (node (ref "R13_PINH") (pin "2") (pinfunction "2_2") (pintype "passive"))
      (node (ref "SENSOR2") (pin "2") (pinfunction "CSB_2") (pintype "input"))
      (node (ref "SENSOR2") (pin "6") (pinfunction "VDDIO_6") (pintype "power_in"))
      (node (ref "SENSOR2") (pin "8") (pinfunction "VDD_8") (pintype "power_in"))
      (node (ref "U2") (pin "17") (pinfunction "IO19_17") (pintype "bidirectional"))
    )
    (net (code "17") (name "INT_RTC") (class "Default")
      (node (ref "R15_PINH1") (pin "1") (pinfunction "1_1") (pintype "passive"))
      (node (ref "TP_INT_RTC") (pin "TP") (pinfunction "TP_TP") (pintype "input"))
      (node (ref "U2") (pin "8") (pinfunction "IO0_8") (pintype "bidirectional"))
      (node (ref "U5") (pin "3") (pinfunction "SQW/~{INT}_3") (pintype "output"))
    )
    (net (code "18") (name "IO{slash}BOOT") (class "Default")
      (node (ref "BOOT_BUTTON") (pin "3") (pinfunction "3_3") (pintype "passive"))
      (node (ref "BOOT_BUTTON") (pin "4") (pinfunction "4_4") (pintype "passive"))
      (node (ref "C24") (pin "1") (pinfunction "1_1") (pintype "passive"))
      (node (ref "R_BOOT") (pin "1") (pinfunction "1_1") (pintype "passive"))
      (node (ref "U2") (pin "15") (pinfunction "IO9_15") (pintype "bidirectional"))
    )
    (net (code "19") (name "IO{slash}CHANGE") (class "Default")
      (node (ref "C25") (pin "1") (pinfunction "1_1") (pintype "passive"))
      (node (ref "CHANGE_BUTTON") (pin "3") (pinfunction "3_3") (pintype "passive"))
      (node (ref "CHANGE_BUTTON") (pin "4") (pinfunction "4_4") (pintype "passive"))
      (node (ref "R_CHANGE") (pin "1") (pinfunction "1_1") (pintype "passive"))
      (node (ref "U2") (pin "23") (pinfunction "IO15_23") (pintype "bidirectional"))
    )
    (net (code "20") (name "MISO") (class "Default")
      (node (ref "D7") (pin "1") (pinfunction "1_1") (pintype "passive"))
      (node (ref "J2") (pin "P7") (pinfunction "DAT0_P7") (pintype "bidirectional"))
      (node (ref "R16") (pin "1") (pinfunction "1_1") (pintype "passive"))
      (node (ref "TP_MISO") (pin "TP") (pinfunction "TP_TP") (pintype "input"))
      (node (ref "U2") (pin "27") (pinfunction "IO2_27") (pintype "bidirectional"))
      (node (ref "U6") (pin "2") (pinfunction "DO(IO1)_2") (pintype "bidirectional"))
    )
    (net (code "21") (name "MOSI") (class "Default")
      (node (ref "D8") (pin "1") (pinfunction "1_1") (pintype "passive"))
      (node (ref "J2") (pin "P3") (pinfunction "CMD_P3") (pintype "bidirectional"))
      (node (ref "J3") (pin "14") (pinfunction "14_14") (pintype "bidirectional"))
      (node (ref "R17") (pin "1") (pinfunction "1_1") (pintype "passive"))
      (node (ref "TP_MOSI") (pin "TP") (pinfunction "TP_TP") (pintype "input"))
      (node (ref "U2") (pin "7") (pinfunction "IO7_7") (pintype "bidirectional"))
      (node (ref "U6") (pin "5") (pinfunction "DI(IO0)_5") (pintype "bidirectional"))
    )
    (net (code "22") (name "Net-(CHG_LED-PadC)") (class "Default")
      (node (ref "CHG_LED") (pin "C") (pinfunction "C_C") (pintype "passive"))
      (node (ref "R8BAT") (pin "1") (pinfunction "1_1") (pintype "passive"))
    )
    (net (code "23") (name "Net-(D2-CATHODE)") (class "Default")
      (node (ref "C3BAT") (pin "1") (pinfunction "1_1") (pintype "passive"))
      (node (ref "D2") (pin "1") (pinfunction "CATHODE_1") (pintype "bidirectional"))
      (node (ref "IC1") (pin "1") (pinfunction "VIN_1") (pintype "bidirectional"))
      (node (ref "IC1") (pin "3") (pinfunction "CE_3") (pintype "bidirectional"))
      (node (ref "Q1") (pin "2") (pinfunction "S_2") (pintype "bidirectional"))
    )
    (net (code "24") (name "Net-(D4-K)") (class "Default")
      (node (ref "C8") (pin "1") (pinfunction "1_1") (pintype "passive"))
      (node (ref "D4") (pin "1") (pinfunction "K_1") (pintype "bidirectional"))
      (node (ref "D5") (pin "2") (pinfunction "A_2") (pintype "bidirectional"))
    )
    (net (code "25") (name "Net-(D6-CATHODE)") (class "Default")
      (node (ref "D6") (pin "1") (pinfunction "CATHODE_1") (pintype "bidirectional"))
      (node (ref "R_CAPACITOR") (pin "2") (pinfunction "2_2") (pintype "passive"))
    )
    (net (code "26") (name "Net-(EPD_C1-Pad2)") (class "Default")
      (node (ref "EPD_C1") (pin "2") (pinfunction "2_2") (pintype "passive"))
      (node (ref "J3") (pin "4") (pinfunction "4_4") (pintype "bidirectional"))
    )
    (net (code "27") (name "Net-(EPD_C2-Pad2)") (class "Default")
      (node (ref "EPD_C2") (pin "2") (pinfunction "2_2") (pintype "passive"))
      (node (ref "J3") (pin "5") (pinfunction "5_5") (pintype "bidirectional"))
    )
    (net (code "28") (name "Net-(EPD_C6-Pad2)") (class "Default")
      (node (ref "EPD_C6") (pin "2") (pinfunction "2_2") (pintype "passive"))
      (node (ref "J3") (pin "18") (pinfunction "18_18") (pintype "bidirectional"))
    )
    (net (code "29") (name "Net-(EPD_C7-Pad2)") (class "Default")
      (node (ref "EPD_C7") (pin "2") (pinfunction "2_2") (pintype "passive"))
      (node (ref "J3") (pin "19") (pinfunction "19_19") (pintype "bidirectional"))
    )
    (net (code "30") (name "Net-(EPD_C8-Pad2)") (class "Default")
      (node (ref "EPD_C8") (pin "2") (pinfunction "2_2") (pintype "passive"))
      (node (ref "J3") (pin "20") (pinfunction "20_20") (pintype "bidirectional"))
    )
    (net (code "31") (name "Net-(EPD_C10-Pad2)") (class "Default")
      (node (ref "EPD_C10") (pin "2") (pinfunction "2_2") (pintype "passive"))
      (node (ref "J3") (pin "22") (pinfunction "22_22") (pintype "bidirectional"))
    )
    (net (code "32") (name "Net-(EPD_C12-Pad2)") (class "Default")
      (node (ref "EPD_C12") (pin "2") (pinfunction "2_2") (pintype "passive"))
      (node (ref "J3") (pin "24") (pinfunction "24_24") (pintype "bidirectional"))
    )
    (net (code "33") (name "Net-(IC2-CT)") (class "Default")
      (node (ref "C_DELAY") (pin "1") (pinfunction "1_1") (pintype "passive"))
      (node (ref "IC2") (pin "5") (pinfunction "CT_5") (pintype "bidirectional"))
    )
    (net (code "34") (name "Net-(J1-PadA5)") (class "Default")
      (node (ref "J1") (pin "A5") (pinfunction "A5_A5") (pintype "bidirectional"))
      (node (ref "R2USB") (pin "2") (pinfunction "2_2") (pintype "passive"))
    )
    (net (code "35") (name "Net-(J1-PadB5)") (class "Default")
      (node (ref "J1") (pin "B5") (pinfunction "B5_B5") (pintype "bidirectional"))
      (node (ref "R3USB1") (pin "1") (pinfunction "1_1") (pintype "passive"))
    )
    (net (code "36") (name "Net-(U1-PROG)") (class "Default")
      (node (ref "R9BAT") (pin "2") (pinfunction "2_2") (pintype "passive"))
      (node (ref "U1") (pin "5") (pinfunction "PROG_5") (pintype "input"))
    )
    (net (code "37") (name "Net-(U1-STAT)") (class "Default")
      (node (ref "R8BAT") (pin "2") (pinfunction "2_2") (pintype "passive"))
      (node (ref "U1") (pin "1") (pinfunction "STAT_1") (pintype "output"))
    )
    (net (code "38") (name "PREVGH") (class "Default")
      (node (ref "D3") (pin "1") (pinfunction "K_1") (pintype "bidirectional"))
      (node (ref "EPD_C9") (pin "2") (pinfunction "2_2") (pintype "passive"))
      (node (ref "J3") (pin "21") (pinfunction "21_21") (pintype "bidirectional"))
    )
    (net (code "39") (name "PREVGL") (class "Default")
      (node (ref "D4") (pin "2") (pinfunction "A_2") (pintype "bidirectional"))
      (node (ref "EPD_C11") (pin "2") (pinfunction "2_2") (pintype "passive"))
      (node (ref "J3") (pin "23") (pinfunction "23_23") (pintype "bidirectional"))
    )
    (net (code "40") (name "RESE") (class "Default")
      (node (ref "J3") (pin "3") (pinfunction "3_3") (pintype "bidirectional"))
      (node (ref "Q2") (pin "2") (pinfunction "S_2") (pintype "bidirectional"))
      (node (ref "R7") (pin "2") (pinfunction "2_2") (pintype "passive"))
    )
    (net (code "41") (name "RESE'") (class "Default")
      (node (ref "R5") (pin "2") (pinfunction "2_2") (pintype "passive"))
      (node (ref "R7") (pin "1") (pinfunction "1_1") (pintype "passive"))
      (node (ref "SJ1") (pin "2") (pinfunction "2_2") (pintype "passive"))
    )
    (net (code "42") (name "RESET") (class "Default")
      (node (ref "C23") (pin "1") (pinfunction "1_1") (pintype "passive"))
      (node (ref "IC2") (pin "1") (pinfunction "VOUT_1") (pintype "bidirectional"))
      (node (ref "RESET_BUTTON") (pin "3") (pinfunction "3_3") (pintype "passive"))
      (node (ref "RESET_BUTTON") (pin "4") (pinfunction "4_4") (pintype "passive"))
      (node (ref "R_RESET") (pin "1") (pinfunction "1_1") (pintype "passive"))
      (node (ref "U2") (pin "3") (pinfunction "EN_3") (pintype "input"))
    )
    (net (code "43") (name "RTC_RST") (class "Default")
      (node (ref "U2") (pin "16") (pinfunction "IO18_16") (pintype "bidirectional"))
      (node (ref "U5") (pin "4") (pinfunction "~{RST}_4") (pintype "input"))
    )
    (net (code "44") (name "RX") (class "Default")
      (node (ref "TP_RX") (pin "TP") (pinfunction "TP_TP") (pintype "input"))
      (node (ref "U2") (pin "24") (pinfunction "RXD0/GPIO17_24") (pintype "bidirectional"))
    )
    (net (code "45") (name "SCK") (class "Default")
      (node (ref "D9") (pin "1") (pinfunction "1_1") (pintype "passive"))
      (node (ref "J2") (pin "P5") (pinfunction "CLK_P5") (pintype "bidirectional"))
      (node (ref "J3") (pin "13") (pinfunction "13_13") (pintype "bidirectional"))
      (node (ref "R18") (pin "1") (pinfunction "1_1") (pintype "passive"))
      (node (ref "TP_SCK") (pin "TP") (pinfunction "TP_TP") (pintype "input"))
      (node (ref "U2") (pin "6") (pinfunction "IO6_6") (pintype "bidirectional"))
      (node (ref "U6") (pin "6") (pinfunction "CLK_6") (pintype "input"))
    )
    (net (code "46") (name "SCL") (class "Default")
      (node (ref "J4") (pin "4") (pinfunction "4_4") (pintype "passive"))
      (node (ref "R12_PINH") (pin "1") (pinfunction "1_1") (pintype "passive"))
      (node (ref "SENSOR2") (pin "4") (pinfunction "SCK_4") (pintype "input"))
      (node (ref "U2") (pin "20") (pinfunction "IO22_20") (pintype "bidirectional"))
      (node (ref "U4") (pin "7") (pinfunction "SCL_7") (pintype "input"))
      (node (ref "U5") (pin "16") (pinfunction "SCL_16") (pintype "input"))
    )
    (net (code "47") (name "SDA") (class "Default")
      (node (ref "J4") (pin "3") (pinfunction "3_3") (pintype "passive"))
      (node (ref "R13_PINH") (pin "1") (pinfunction "1_1") (pintype "passive"))
      (node (ref "SENSOR2") (pin "3") (pinfunction "SDI_3") (pintype "bidirectional"))
      (node (ref "U2") (pin "19") (pinfunction "IO21_19") (pintype "bidirectional"))
      (node (ref "U4") (pin "8") (pinfunction "SDA_8") (pintype "bidirectional"))
      (node (ref "U5") (pin "15") (pinfunction "SDA_15") (pintype "bidirectional"))
    )
    (net (code "48") (name "SRC") (class "Default")
      (node (ref "C8") (pin "2") (pinfunction "2_2") (pintype "passive"))
      (node (ref "D3") (pin "2") (pinfunction "A_2") (pintype "bidirectional"))
      (node (ref "L2") (pin "1") (pinfunction "1_1") (pintype "passive"))
      (node (ref "Q2") (pin "3") (pinfunction "D_3") (pintype "bidirectional"))
    )
    (net (code "49") (name "SS_SD") (class "Default")
      (node (ref "D12") (pin "1") (pinfunction "1_1") (pintype "passive"))
      (node (ref "J2") (pin "P2") (pinfunction "CD/DAT3_P2") (pintype "bidirectional"))
      (node (ref "R21") (pin "1") (pinfunction "1_1") (pintype "passive"))
      (node (ref "U2") (pin "4") (pinfunction "IO4_4") (pintype "bidirectional"))
    )
    (net (code "50") (name "TX") (class "Default")
      (node (ref "TP_TX") (pin "TP") (pinfunction "TP_TP") (pintype "input"))
      (node (ref "U2") (pin "25") (pinfunction "TXD0/GPIO16_25") (pintype "bidirectional"))
    )
    (net (code "51") (name "USB_D+") (class "Default")
      (node (ref "D1") (pin "1") (pinfunction "I/O1_1_1") (pintype "bidirectional"))
      (node (ref "U2") (pin "14") (pinfunction "IO13_14") (pintype "bidirectional"))
    )
    (net (code "52") (name "USB_D-") (class "Default")
      (node (ref "D1") (pin "3") (pinfunction "I/O2_1_3") (pintype "bidirectional"))
      (node (ref "U2") (pin "13") (pinfunction "IO12_13") (pintype "bidirectional"))
    )
    (net (code "53") (name "VBAT") (class "Default")
      (node (ref "C10BAT") (pin "1") (pinfunction "1_1") (pintype "passive"))
      (node (ref "Q1") (pin "3") (pinfunction "D_3") (pintype "bidirectional"))
      (node (ref "TP_VBAT") (pin "TP") (pinfunction "TP_TP") (pintype "input"))
      (node (ref "U1") (pin "3") (pinfunction "VBAT_3") (pintype "power_in"))
      (node (ref "U4") (pin "2") (pinfunction "CELL_2") (pintype "power_in"))
      (node (ref "U4") (pin "3") (pinfunction "VDD_3") (pintype "power_in"))
    )
    (net (code "54") (name "VBUS") (class "Default")
      (node (ref "C1USB") (pin "1") (pinfunction "1_1") (pintype "passive"))
      (node (ref "C2USB1") (pin "1") (pinfunction "1_1") (pintype "passive"))
      (node (ref "C9BAT") (pin "1") (pinfunction "1_1") (pintype "passive"))
      (node (ref "CHG_LED") (pin "A") (pinfunction "A_A") (pintype "passive"))
      (node (ref "D1") (pin "5") (pinfunction "VBUS_5") (pintype "bidirectional"))
      (node (ref "D2") (pin "2") (pinfunction "ANODE_2") (pintype "bidirectional"))
      (node (ref "Q1") (pin "1") (pinfunction "G_1") (pintype "bidirectional"))
      (node (ref "R1") (pin "2") (pinfunction "2_2") (pintype "passive"))
      (node (ref "R4PWRUSB1") (pin "2") (pinfunction "2_2") (pintype "passive"))
      (node (ref "TP_VBUS") (pin "TP") (pinfunction "TP_TP") (pintype "input"))
      (node (ref "U1") (pin "4") (pinfunction "VIN_4") (pintype "power_in"))
    )
    (net (code "55") (name "VRTC") (class "Default")
      (node (ref "C26") (pin "1") (pinfunction "1_1") (pintype "passive"))
      (node (ref "R_CAPACITOR") (pin "1") (pinfunction "1_1") (pintype "passive"))
      (node (ref "SUPERCAP") (pin "1") (pinfunction "1_1") (pintype "passive"))
      (node (ref "U5") (pin "14") (pinfunction "VBAT_14") (pintype "power_in"))
    )
    (net (code "56") (name "unconnected-(IC1-NC-Pad4)") (class "Default")
      (node (ref "IC1") (pin "4") (pinfunction "NC_4") (pintype "no_connect"))
    )
    (net (code "57") (name "unconnected-(IC2-NC-Pad4)") (class "Default")
      (node (ref "IC2") (pin "4") (pinfunction "NC_4") (pintype "no_connect"))
    )
    (net (code "58") (name "unconnected-(J1-PadA8)") (class "Default")
      (node (ref "J1") (pin "A8") (pinfunction "A8_A8") (pintype "bidirectional"))
    )
    (net (code "59") (name "unconnected-(J1-PadB8)") (class "Default")
      (node (ref "J1") (pin "B8") (pinfunction "B8_B8") (pintype "bidirectional"))
    )
    (net (code "60") (name "unconnected-(J2-DAT1-PadP8)") (class "Default")
      (node (ref "J2") (pin "P8") (pinfunction "DAT1_P8") (pintype "bidirectional"))
    )
    (net (code "61") (name "unconnected-(J2-DAT2-PadP1)") (class "Default")
      (node (ref "J2") (pin "P1") (pinfunction "DAT2_P1") (pintype "bidirectional"))
    )
    (net (code "62") (name "unconnected-(J2-DETECTION_1-PadS1)") (class "Default")
      (node (ref "J2") (pin "S1") (pinfunction "DETECTION_1_S1") (pintype "bidirectional"))
    )
    (net (code "63") (name "unconnected-(J2-DETECTION_2-PadS2)") (class "Default")
      (node (ref "J2") (pin "S2") (pinfunction "DETECTION_2_S2") (pintype "bidirectional"))
    )
    (net (code "64") (name "unconnected-(J3-Pad1)") (class "Default")
      (node (ref "J3") (pin "1") (pinfunction "1_1") (pintype "bidirectional"))
    )
    (net (code "65") (name "unconnected-(J3-Pad6)") (class "Default")
      (node (ref "J3") (pin "6") (pinfunction "6_6") (pintype "bidirectional"))
    )
    (net (code "66") (name "unconnected-(J3-Pad7)") (class "Default")
      (node (ref "J3") (pin "7") (pinfunction "7_7") (pintype "bidirectional"))
    )
    (net (code "67") (name "unconnected-(U2-NC-Pad22)") (class "Default")
      (node (ref "U2") (pin "22") (pinfunction "NC_22") (pintype "no_connect"))
    )
    (net (code "68") (name "unconnected-(U4-~{ALERT}-Pad5)") (class "Default")
      (node (ref "U4") (pin "5") (pinfunction "~{ALERT}_5") (pintype "output"))
    )
  )
)
